# smd-led.net
KiCad netlist of a schematic drawn in EAGLE
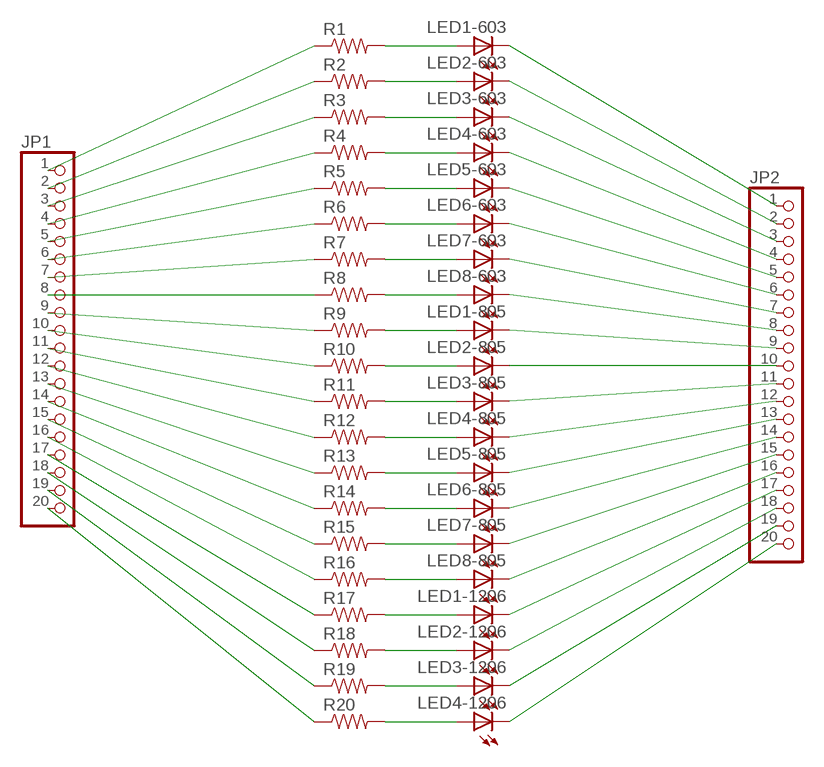
[diagram p0: schematic, sheet 1]

(export (version "E")
  (design (tool "Eeschema 10.0.6"))
  (components
    (comp (ref "JP1")
      (value "PINHD-1X20")
      (footprint "eagle-import:1X20")
      (libsource (lib "eagle-import") (part "PINHD-1X20"))
    )
    (comp (ref "JP2")
      (value "PINHD-1X20")
      (footprint "eagle-import:1X20")
      (libsource (lib "eagle-import") (part "PINHD-1X20"))
    )
    (comp (ref "LED1-603")
      (value "LEDSML0603")
      (footprint "eagle-import:SML0603")
      (libsource (lib "eagle-import") (part "LEDSML0603"))
    )
    (comp (ref "LED1-805")
      (value "LEDSML0805")
      (footprint "eagle-import:SML0805")
      (libsource (lib "eagle-import") (part "LEDSML0805"))
    )
    (comp (ref "LED1-1206")
      (value "LEDSML1206")
      (footprint "eagle-import:SML1206")
      (libsource (lib "eagle-import") (part "LEDSML1206"))
    )
    (comp (ref "LED2-603")
      (value "LEDSML0603")
      (footprint "eagle-import:SML0603")
      (libsource (lib "eagle-import") (part "LEDSML0603"))
    )
    (comp (ref "LED2-805")
      (value "LEDSML0805")
      (footprint "eagle-import:SML0805")
      (libsource (lib "eagle-import") (part "LEDSML0805"))
    )
    (comp (ref "LED2-1206")
      (value "LEDSML1206")
      (footprint "eagle-import:SML1206")
      (libsource (lib "eagle-import") (part "LEDSML1206"))
    )
    (comp (ref "LED3-603")
      (value "LEDSML0603")
      (footprint "eagle-import:SML0603")
      (libsource (lib "eagle-import") (part "LEDSML0603"))
    )
    (comp (ref "LED3-805")
      (value "LEDSML0805")
      (footprint "eagle-import:SML0805")
      (libsource (lib "eagle-import") (part "LEDSML0805"))
    )
    (comp (ref "LED3-1206")
      (value "LEDSML1206")
      (footprint "eagle-import:SML1206")
      (libsource (lib "eagle-import") (part "LEDSML1206"))
    )
    (comp (ref "LED4-603")
      (value "LEDSML0603")
      (footprint "eagle-import:SML0603")
      (libsource (lib "eagle-import") (part "LEDSML0603"))
    )
    (comp (ref "LED4-805")
      (value "LEDSML0805")
      (footprint "eagle-import:SML0805")
      (libsource (lib "eagle-import") (part "LEDSML0805"))
    )
    (comp (ref "LED4-1206")
      (value "LEDSML1206")
      (footprint "eagle-import:SML1206")
      (libsource (lib "eagle-import") (part "LEDSML1206"))
    )
    (comp (ref "LED5-603")
      (value "LEDSML0603")
      (footprint "eagle-import:SML0603")
      (libsource (lib "eagle-import") (part "LEDSML0603"))
    )
    (comp (ref "LED5-805")
      (value "LEDSML0805")
      (footprint "eagle-import:SML0805")
      (libsource (lib "eagle-import") (part "LEDSML0805"))
    )
    (comp (ref "LED6-603")
      (value "LEDSML0603")
      (footprint "eagle-import:SML0603")
      (libsource (lib "eagle-import") (part "LEDSML0603"))
    )
    (comp (ref "LED6-805")
      (value "LEDSML0805")
      (footprint "eagle-import:SML0805")
      (libsource (lib "eagle-import") (part "LEDSML0805"))
    )
    (comp (ref "LED7-603")
      (value "LEDSML0603")
      (footprint "eagle-import:SML0603")
      (libsource (lib "eagle-import") (part "LEDSML0603"))
    )
    (comp (ref "LED7-805")
      (value "LEDSML0805")
      (footprint "eagle-import:SML0805")
      (libsource (lib "eagle-import") (part "LEDSML0805"))
    )
    (comp (ref "LED8-603")
      (value "LEDSML0603")
      (footprint "eagle-import:SML0603")
      (libsource (lib "eagle-import") (part "LEDSML0603"))
    )
    (comp (ref "LED8-805")
      (value "LEDSML0805")
      (footprint "eagle-import:SML0805")
      (libsource (lib "eagle-import") (part "LEDSML0805"))
    )
    (comp (ref "R1")
      (value "RESISTOR0805-RES")
      (footprint "eagle-import:0805")
      (libsource (lib "eagle-import") (part "RESISTOR0805-RES"))
    )
    (comp (ref "R2")
      (value "RESISTOR0805-RES")
      (footprint "eagle-import:0805")
      (libsource (lib "eagle-import") (part "RESISTOR0805-RES"))
    )
    (comp (ref "R3")
      (value "RESISTOR0805-RES")
      (footprint "eagle-import:0805")
      (libsource (lib "eagle-import") (part "RESISTOR0805-RES"))
    )
    (comp (ref "R4")
      (value "RESISTOR0805-RES")
      (footprint "eagle-import:0805")
      (libsource (lib "eagle-import") (part "RESISTOR0805-RES"))
    )
    (comp (ref "R5")
      (value "RESISTOR0805-RES")
      (footprint "eagle-import:0805")
      (libsource (lib "eagle-import") (part "RESISTOR0805-RES"))
    )
    (comp (ref "R6")
      (value "RESISTOR0805-RES")
      (footprint "eagle-import:0805")
      (libsource (lib "eagle-import") (part "RESISTOR0805-RES"))
    )
    (comp (ref "R7")
      (value "RESISTOR0805-RES")
      (footprint "eagle-import:0805")
      (libsource (lib "eagle-import") (part "RESISTOR0805-RES"))
    )
    (comp (ref "R8")
      (value "RESISTOR0805-RES")
      (footprint "eagle-import:0805")
      (libsource (lib "eagle-import") (part "RESISTOR0805-RES"))
    )
    (comp (ref "R9")
      (value "RESISTOR0805-RES")
      (footprint "eagle-import:0805")
      (libsource (lib "eagle-import") (part "RESISTOR0805-RES"))
    )
    (comp (ref "R10")
      (value "RESISTOR0805-RES")
      (footprint "eagle-import:0805")
      (libsource (lib "eagle-import") (part "RESISTOR0805-RES"))
    )
    (comp (ref "R11")
      (value "RESISTOR0805-RES")
      (footprint "eagle-import:0805")
      (libsource (lib "eagle-import") (part "RESISTOR0805-RES"))
    )
    (comp (ref "R12")
      (value "RESISTOR0805-RES")
      (footprint "eagle-import:0805")
      (libsource (lib "eagle-import") (part "RESISTOR0805-RES"))
    )
    (comp (ref "R13")
      (value "RESISTOR0805-RES")
      (footprint "eagle-import:0805")
      (libsource (lib "eagle-import") (part "RESISTOR0805-RES"))
    )
    (comp (ref "R14")
      (value "RESISTOR0805-RES")
      (footprint "eagle-import:0805")
      (libsource (lib "eagle-import") (part "RESISTOR0805-RES"))
    )
    (comp (ref "R15")
      (value "RESISTOR0805-RES")
      (footprint "eagle-import:0805")
      (libsource (lib "eagle-import") (part "RESISTOR0805-RES"))
    )
    (comp (ref "R16")
      (value "RESISTOR0805-RES")
      (footprint "eagle-import:0805")
      (libsource (lib "eagle-import") (part "RESISTOR0805-RES"))
    )
    (comp (ref "R17")
      (value "RESISTOR0805-RES")
      (footprint "eagle-import:0805")
      (libsource (lib "eagle-import") (part "RESISTOR0805-RES"))
    )
    (comp (ref "R18")
      (value "RESISTOR0805-RES")
      (footprint "eagle-import:0805")
      (libsource (lib "eagle-import") (part "RESISTOR0805-RES"))
    )
    (comp (ref "R19")
      (value "RESISTOR0805-RES")
      (footprint "eagle-import:0805")
      (libsource (lib "eagle-import") (part "RESISTOR0805-RES"))
    )
    (comp (ref "R20")
      (value "RESISTOR0805-RES")
      (footprint "eagle-import:0805")
      (libsource (lib "eagle-import") (part "RESISTOR0805-RES"))
    )
  )
  (nets
    (net (code "1") (name "Net-(JP1-Pad1)") (class "Default")
      (node (ref "JP1") (pin "1") (pinfunction "1_1") (pintype "passive"))
      (node (ref "R1") (pin "1") (pinfunction "1_1") (pintype "passive"))
    )
    (net (code "2") (name "Net-(JP1-Pad2)") (class "Default")
      (node (ref "JP1") (pin "2") (pinfunction "2_2") (pintype "passive"))
      (node (ref "R2") (pin "1") (pinfunction "1_1") (pintype "passive"))
    )
    (net (code "3") (name "Net-(JP1-Pad3)") (class "Default")
      (node (ref "JP1") (pin "3") (pinfunction "3_3") (pintype "passive"))
      (node (ref "R3") (pin "1") (pinfunction "1_1") (pintype "passive"))
    )
    (net (code "4") (name "Net-(JP1-Pad4)") (class "Default")
      (node (ref "JP1") (pin "4") (pinfunction "4_4") (pintype "passive"))
      (node (ref "R4") (pin "1") (pinfunction "1_1") (pintype "passive"))
    )
    (net (code "5") (name "Net-(JP1-Pad5)") (class "Default")
      (node (ref "JP1") (pin "5") (pinfunction "5_5") (pintype "passive"))
      (node (ref "R5") (pin "1") (pinfunction "1_1") (pintype "passive"))
    )
    (net (code "6") (name "Net-(JP1-Pad6)") (class "Default")
      (node (ref "JP1") (pin "6") (pinfunction "6_6") (pintype "passive"))
      (node (ref "R6") (pin "1") (pinfunction "1_1") (pintype "passive"))
    )
    (net (code "7") (name "Net-(JP1-Pad7)") (class "Default")
      (node (ref "JP1") (pin "7") (pinfunction "7_7") (pintype "passive"))
      (node (ref "R7") (pin "1") (pinfunction "1_1") (pintype "passive"))
    )
    (net (code "8") (name "Net-(JP1-Pad8)") (class "Default")
      (node (ref "JP1") (pin "8") (pinfunction "8_8") (pintype "passive"))
      (node (ref "R8") (pin "1") (pinfunction "1_1") (pintype "passive"))
    )
    (net (code "9") (name "Net-(JP1-Pad9)") (class "Default")
      (node (ref "JP1") (pin "9") (pinfunction "9_9") (pintype "passive"))
      (node (ref "R9") (pin "1") (pinfunction "1_1") (pintype "passive"))
    )
    (net (code "10") (name "Net-(JP1-Pad10)") (class "Default")
      (node (ref "JP1") (pin "10") (pinfunction "10_10") (pintype "passive"))
      (node (ref "R10") (pin "1") (pinfunction "1_1") (pintype "passive"))
    )
    (net (code "11") (name "Net-(JP1-Pad11)") (class "Default")
      (node (ref "JP1") (pin "11") (pinfunction "11_11") (pintype "passive"))
      (node (ref "R11") (pin "1") (pinfunction "1_1") (pintype "passive"))
    )
    (net (code "12") (name "Net-(JP1-Pad12)") (class "Default")
      (node (ref "JP1") (pin "12") (pinfunction "12_12") (pintype "passive"))
      (node (ref "R12") (pin "1") (pinfunction "1_1") (pintype "passive"))
    )
    (net (code "13") (name "Net-(JP1-Pad13)") (class "Default")
      (node (ref "JP1") (pin "13") (pinfunction "13_13") (pintype "passive"))
      (node (ref "R13") (pin "1") (pinfunction "1_1") (pintype "passive"))
    )
    (net (code "14") (name "Net-(JP1-Pad14)") (class "Default")
      (node (ref "JP1") (pin "14") (pinfunction "14_14") (pintype "passive"))
      (node (ref "R14") (pin "1") (pinfunction "1_1") (pintype "passive"))
    )
    (net (code "15") (name "Net-(JP1-Pad15)") (class "Default")
      (node (ref "JP1") (pin "15") (pinfunction "15_15") (pintype "passive"))
      (node (ref "R15") (pin "1") (pinfunction "1_1") (pintype "passive"))
    )
    (net (code "16") (name "Net-(JP1-Pad16)") (class "Default")
      (node (ref "JP1") (pin "16") (pinfunction "16_16") (pintype "passive"))
      (node (ref "R16") (pin "1") (pinfunction "1_1") (pintype "passive"))
    )
    (net (code "17") (name "Net-(JP1-Pad17)") (class "Default")
      (node (ref "JP1") (pin "17") (pinfunction "17_17") (pintype "passive"))
      (node (ref "R17") (pin "1") (pinfunction "1_1") (pintype "passive"))
    )
    (net (code "18") (name "Net-(JP1-Pad18)") (class "Default")
      (node (ref "JP1") (pin "18") (pinfunction "18_18") (pintype "passive"))
      (node (ref "R18") (pin "1") (pinfunction "1_1") (pintype "passive"))
    )
    (net (code "19") (name "Net-(JP1-Pad19)") (class "Default")
      (node (ref "JP1") (pin "19") (pinfunction "19_19") (pintype "passive"))
      (node (ref "R19") (pin "1") (pinfunction "1_1") (pintype "passive"))
    )
    (net (code "20") (name "Net-(JP1-Pad20)") (class "Default")
      (node (ref "JP1") (pin "20") (pinfunction "20_20") (pintype "passive"))
      (node (ref "R20") (pin "1") (pinfunction "1_1") (pintype "passive"))
    )
    (net (code "21") (name "Net-(JP2-Pad1)") (class "Default")
      (node (ref "JP2") (pin "1") (pinfunction "1_1") (pintype "passive"))
      (node (ref "LED1-603") (pin "C") (pinfunction "C_C") (pintype "passive"))
    )
    (net (code "22") (name "Net-(JP2-Pad2)") (class "Default")
      (node (ref "JP2") (pin "2") (pinfunction "2_2") (pintype "passive"))
      (node (ref "LED2-603") (pin "C") (pinfunction "C_C") (pintype "passive"))
    )
    (net (code "23") (name "Net-(JP2-Pad3)") (class "Default")
      (node (ref "JP2") (pin "3") (pinfunction "3_3") (pintype "passive"))
      (node (ref "LED3-603") (pin "C") (pinfunction "C_C") (pintype "passive"))
    )
    (net (code "24") (name "Net-(JP2-Pad4)") (class "Default")
      (node (ref "JP2") (pin "4") (pinfunction "4_4") (pintype "passive"))
      (node (ref "LED4-603") (pin "C") (pinfunction "C_C") (pintype "passive"))
    )
    (net (code "25") (name "Net-(JP2-Pad5)") (class "Default")
      (node (ref "JP2") (pin "5") (pinfunction "5_5") (pintype "passive"))
      (node (ref "LED5-603") (pin "C") (pinfunction "C_C") (pintype "passive"))
    )
    (net (code "26") (name "Net-(JP2-Pad6)") (class "Default")
      (node (ref "JP2") (pin "6") (pinfunction "6_6") (pintype "passive"))
      (node (ref "LED6-603") (pin "C") (pinfunction "C_C") (pintype "passive"))
    )
    (net (code "27") (name "Net-(JP2-Pad7)") (class "Default")
      (node (ref "JP2") (pin "7") (pinfunction "7_7") (pintype "passive"))
      (node (ref "LED7-603") (pin "C") (pinfunction "C_C") (pintype "passive"))
    )
    (net (code "28") (name "Net-(JP2-Pad8)") (class "Default")
      (node (ref "JP2") (pin "8") (pinfunction "8_8") (pintype "passive"))
      (node (ref "LED8-603") (pin "C") (pinfunction "C_C") (pintype "passive"))
    )
    (net (code "29") (name "Net-(JP2-Pad9)") (class "Default")
      (node (ref "JP2") (pin "9") (pinfunction "9_9") (pintype "passive"))
      (node (ref "LED1-805") (pin "C") (pinfunction "C_C") (pintype "passive"))
    )
    (net (code "30") (name "Net-(JP2-Pad10)") (class "Default")
      (node (ref "JP2") (pin "10") (pinfunction "10_10") (pintype "passive"))
      (node (ref "LED2-805") (pin "C") (pinfunction "C_C") (pintype "passive"))
    )
    (net (code "31") (name "Net-(JP2-Pad11)") (class "Default")
      (node (ref "JP2") (pin "11") (pinfunction "11_11") (pintype "passive"))
      (node (ref "LED3-805") (pin "C") (pinfunction "C_C") (pintype "passive"))
    )
    (net (code "32") (name "Net-(JP2-Pad12)") (class "Default")
      (node (ref "JP2") (pin "12") (pinfunction "12_12") (pintype "passive"))
      (node (ref "LED4-805") (pin "C") (pinfunction "C_C") (pintype "passive"))
    )
    (net (code "33") (name "Net-(JP2-Pad13)") (class "Default")
      (node (ref "JP2") (pin "13") (pinfunction "13_13") (pintype "passive"))
      (node (ref "LED5-805") (pin "C") (pinfunction "C_C") (pintype "passive"))
    )
    (net (code "34") (name "Net-(JP2-Pad14)") (class "Default")
      (node (ref "JP2") (pin "14") (pinfunction "14_14") (pintype "passive"))
      (node (ref "LED6-805") (pin "C") (pinfunction "C_C") (pintype "passive"))
    )
    (net (code "35") (name "Net-(JP2-Pad15)") (class "Default")
      (node (ref "JP2") (pin "15") (pinfunction "15_15") (pintype "passive"))
      (node (ref "LED7-805") (pin "C") (pinfunction "C_C") (pintype "passive"))
    )
    (net (code "36") (name "Net-(JP2-Pad16)") (class "Default")
      (node (ref "JP2") (pin "16") (pinfunction "16_16") (pintype "passive"))
      (node (ref "LED8-805") (pin "C") (pinfunction "C_C") (pintype "passive"))
    )
    (net (code "37") (name "Net-(JP2-Pad17)") (class "Default")
      (node (ref "JP2") (pin "17") (pinfunction "17_17") (pintype "passive"))
      (node (ref "LED1-1206") (pin "C") (pinfunction "C_C") (pintype "passive"))
    )
    (net (code "38") (name "Net-(JP2-Pad18)") (class "Default")
      (node (ref "JP2") (pin "18") (pinfunction "18_18") (pintype "passive"))
      (node (ref "LED2-1206") (pin "C") (pinfunction "C_C") (pintype "passive"))
    )
    (net (code "39") (name "Net-(JP2-Pad19)") (class "Default")
      (node (ref "JP2") (pin "19") (pinfunction "19_19") (pintype "passive"))
      (node (ref "LED3-1206") (pin "C") (pinfunction "C_C") (pintype "passive"))
    )
    (net (code "40") (name "Net-(JP2-Pad20)") (class "Default")
      (node (ref "JP2") (pin "20") (pinfunction "20_20") (pintype "passive"))
      (node (ref "LED4-1206") (pin "C") (pinfunction "C_C") (pintype "passive"))
    )
    (net (code "41") (name "Net-(LED1-603-PadA)") (class "Default")
      (node (ref "LED1-603") (pin "A") (pinfunction "A_A") (pintype "passive"))
      (node (ref "R1") (pin "2") (pinfunction "2_2") (pintype "passive"))
    )
    (net (code "42") (name "Net-(LED1-805-PadA)") (class "Default")
      (node (ref "LED1-805") (pin "A") (pinfunction "A_A") (pintype "passive"))
      (node (ref "R9") (pin "2") (pinfunction "2_2") (pintype "passive"))
    )
    (net (code "43") (name "Net-(LED1-1206-PadA)") (class "Default")
      (node (ref "LED1-1206") (pin "A") (pinfunction "A_A") (pintype "passive"))
      (node (ref "R17") (pin "2") (pinfunction "2_2") (pintype "passive"))
    )
    (net (code "44") (name "Net-(LED2-603-PadA)") (class "Default")
      (node (ref "LED2-603") (pin "A") (pinfunction "A_A") (pintype "passive"))
      (node (ref "R2") (pin "2") (pinfunction "2_2") (pintype "passive"))
    )
    (net (code "45") (name "Net-(LED2-805-PadA)") (class "Default")
      (node (ref "LED2-805") (pin "A") (pinfunction "A_A") (pintype "passive"))
      (node (ref "R10") (pin "2") (pinfunction "2_2") (pintype "passive"))
    )
    (net (code "46") (name "Net-(LED2-1206-PadA)") (class "Default")
      (node (ref "LED2-1206") (pin "A") (pinfunction "A_A") (pintype "passive"))
      (node (ref "R18") (pin "2") (pinfunction "2_2") (pintype "passive"))
    )
    (net (code "47") (name "Net-(LED3-603-PadA)") (class "Default")
      (node (ref "LED3-603") (pin "A") (pinfunction "A_A") (pintype "passive"))
      (node (ref "R3") (pin "2") (pinfunction "2_2") (pintype "passive"))
    )
    (net (code "48") (name "Net-(LED3-805-PadA)") (class "Default")
      (node (ref "LED3-805") (pin "A") (pinfunction "A_A") (pintype "passive"))
      (node (ref "R11") (pin "2") (pinfunction "2_2") (pintype "passive"))
    )
    (net (code "49") (name "Net-(LED3-1206-PadA)") (class "Default")
      (node (ref "LED3-1206") (pin "A") (pinfunction "A_A") (pintype "passive"))
      (node (ref "R19") (pin "2") (pinfunction "2_2") (pintype "passive"))
    )
    (net (code "50") (name "Net-(LED4-603-PadA)") (class "Default")
      (node (ref "LED4-603") (pin "A") (pinfunction "A_A") (pintype "passive"))
      (node (ref "R4") (pin "2") (pinfunction "2_2") (pintype "passive"))
    )
    (net (code "51") (name "Net-(LED4-805-PadA)") (class "Default")
      (node (ref "LED4-805") (pin "A") (pinfunction "A_A") (pintype "passive"))
      (node (ref "R12") (pin "2") (pinfunction "2_2") (pintype "passive"))
    )
    (net (code "52") (name "Net-(LED4-1206-PadA)") (class "Default")
      (node (ref "LED4-1206") (pin "A") (pinfunction "A_A") (pintype "passive"))
      (node (ref "R20") (pin "2") (pinfunction "2_2") (pintype "passive"))
    )
    (net (code "53") (name "Net-(LED5-603-PadA)") (class "Default")
      (node (ref "LED5-603") (pin "A") (pinfunction "A_A") (pintype "passive"))
      (node (ref "R5") (pin "2") (pinfunction "2_2") (pintype "passive"))
    )
    (net (code "54") (name "Net-(LED5-805-PadA)") (class "Default")
      (node (ref "LED5-805") (pin "A") (pinfunction "A_A") (pintype "passive"))
      (node (ref "R13") (pin "2") (pinfunction "2_2") (pintype "passive"))
    )
    (net (code "55") (name "Net-(LED6-603-PadA)") (class "Default")
      (node (ref "LED6-603") (pin "A") (pinfunction "A_A") (pintype "passive"))
      (node (ref "R6") (pin "2") (pinfunction "2_2") (pintype "passive"))
    )
    (net (code "56") (name "Net-(LED6-805-PadA)") (class "Default")
      (node (ref "LED6-805") (pin "A") (pinfunction "A_A") (pintype "passive"))
      (node (ref "R14") (pin "2") (pinfunction "2_2") (pintype "passive"))
    )
    (net (code "57") (name "Net-(LED7-603-PadA)") (class "Default")
      (node (ref "LED7-603") (pin "A") (pinfunction "A_A") (pintype "passive"))
      (node (ref "R7") (pin "2") (pinfunction "2_2") (pintype "passive"))
    )
    (net (code "58") (name "Net-(LED7-805-PadA)") (class "Default")
      (node (ref "LED7-805") (pin "A") (pinfunction "A_A") (pintype "passive"))
      (node (ref "R15") (pin "2") (pinfunction "2_2") (pintype "passive"))
    )
    (net (code "59") (name "Net-(LED8-603-PadA)") (class "Default")
      (node (ref "LED8-603") (pin "A") (pinfunction "A_A") (pintype "passive"))
      (node (ref "R8") (pin "2") (pinfunction "2_2") (pintype "passive"))
    )
    (net (code "60") (name "Net-(LED8-805-PadA)") (class "Default")
      (node (ref "LED8-805") (pin "A") (pinfunction "A_A") (pintype "passive"))
      (node (ref "R16") (pin "2") (pinfunction "2_2") (pintype "passive"))
    )
  )
)
